# Header_and_OnboardConponents.net
KiCad netlist of a schematic drawn in Altium Designer
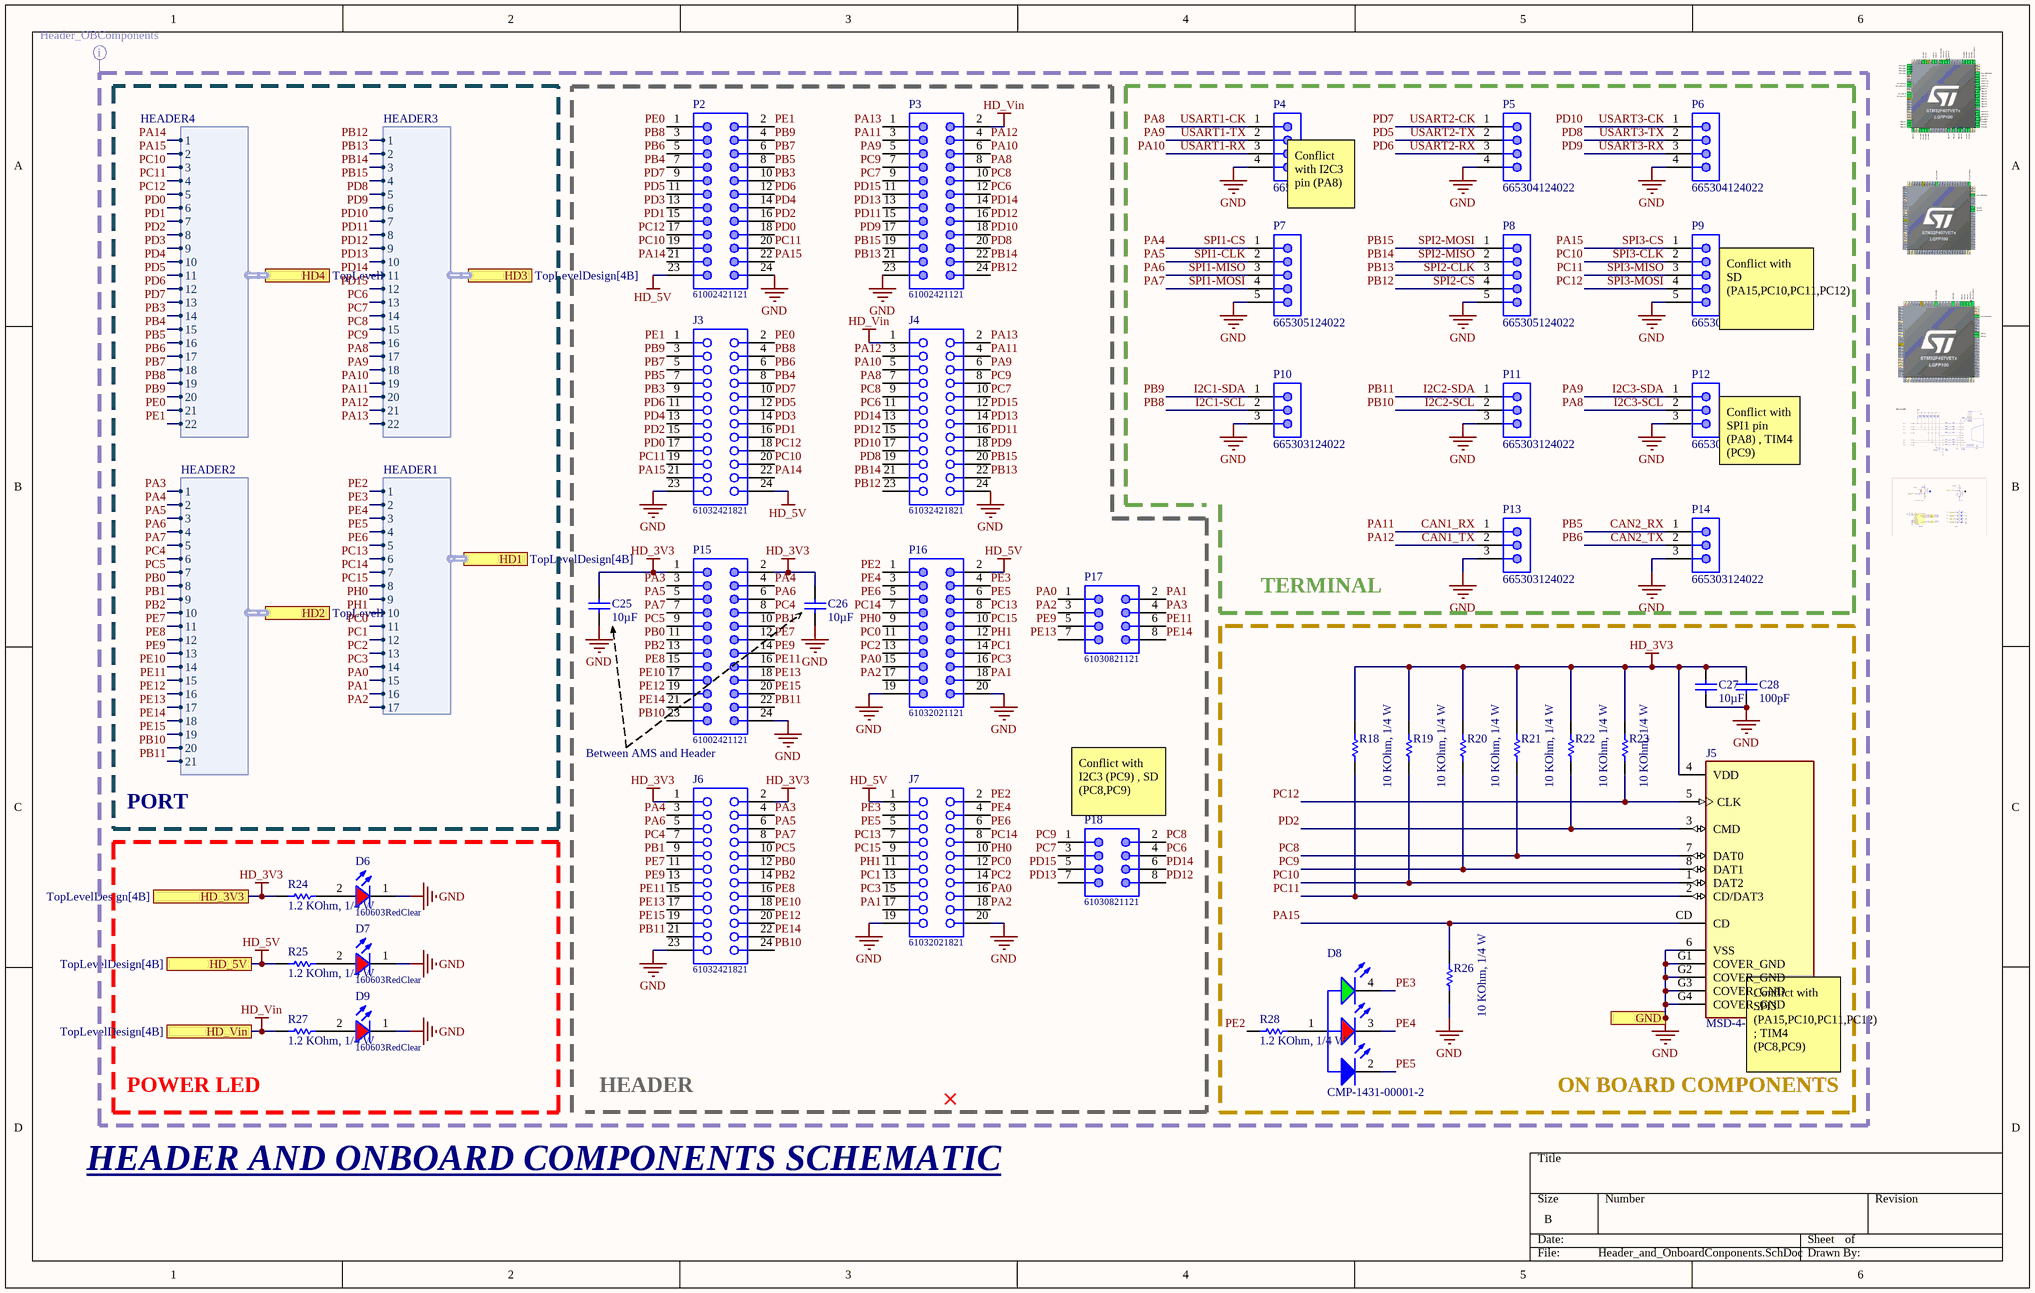
[diagram p0: Header_and_OnboardConponents.SchDoc]

(export (version "E")
  (design (tool "Eeschema 10.0.6"))
  (components
    (comp (ref "C25")
      (value "10µF")
      (footprint "CAP_0603")
      (description "CAP, size 0603, 10 uF, 10 VDC")
      (fields
        (field (name "TOLERANCE") "10%")
        (field (name "Comment") "0106031061010")
        (field (name "SOURCE") "Capacitor_0603_10_percent.SchLib")
      )
      (libsource (lib "Tin Tran") (part "010603475106.3"))
    )
    (comp (ref "C26")
      (value "10µF")
      (footprint "CAP_0603")
      (description "CAP, size 0603, 10 uF, 10 VDC")
      (fields
        (field (name "TOLERANCE") "10%")
        (field (name "Comment") "0106031061010")
        (field (name "SOURCE") "Capacitor_0603_10_percent.SchLib")
      )
      (libsource (lib "Tin Tran") (part "010603475106.3"))
    )
    (comp (ref "C27")
      (value "10µF")
      (footprint "CAP_0603")
      (description "CAP, size 0603, 10 uF, 10 VDC")
      (fields
        (field (name "TOLERANCE") "10%")
        (field (name "Comment") "0106031061010")
        (field (name "SOURCE") "Capacitor_0603_10_percent.SchLib")
      )
      (libsource (lib "Tin Tran") (part "010603475106.3"))
    )
    (comp (ref "C28")
      (value "100pF")
      (footprint "CAP_0603")
      (description "CAP, size 0603, 100 pF, 50 VDC")
      (fields
        (field (name "TOLERANCE") "5%")
        (field (name "Comment") "0106031010550")
        (field (name "SOURCE") "Capacitor_0603_5_percent.SchLib")
      )
      (libsource (lib "Tin Tran") (part "0106036820550"))
    )
    (comp (ref "D6")
      (value "160603RedClear")
      (footprint "WL-SMCW_0603_H=0.7mm")
      (description "WL-SMCW SMT Mono-color Chip LED Waterclear, size 0603, Red, 2V, 140deg")
      (libsource (lib "Tin Tran") (part "160603RedClear"))
    )
    (comp (ref "D7")
      (value "160603RedClear")
      (footprint "WL-SMCW_0603_H=0.7mm")
      (description "WL-SMCW SMT Mono-color Chip LED Waterclear, size 0603, Red, 2V, 140deg")
      (libsource (lib "Tin Tran") (part "160603RedClear"))
    )
    (comp (ref "D8")
      (value "CMP-1431-00001-2")
      (footprint "WL-SFTW_3528_150141M173100")
      (libsource (lib "Tin Tran") (part "CMP-1431-00001-2"))
    )
    (comp (ref "D9")
      (value "160603RedClear")
      (footprint "WL-SMCW_0603_H=0.7mm")
      (description "WL-SMCW SMT Mono-color Chip LED Waterclear, size 0603, Red, 2V, 140deg")
      (libsource (lib "Tin Tran") (part "160603RedClear"))
    )
    (comp (ref "J3")
      (value "61032421821")
      (footprint "61032421821")
      (description "WR-PHD Socket Header, SMT, pitch 2.54mm, Dual Row, Vertical, 24p")
      (fields (field (name "MANUFACTURER") "Wurth Elektronik"))
      (libsource (lib "Tin Tran") (part "613024243121"))
    )
    (comp (ref "J4")
      (value "61032421821")
      (footprint "61032421821")
      (description "WR-PHD Socket Header, SMT, pitch 2.54mm, Dual Row, Vertical, 24p")
      (fields (field (name "MANUFACTURER") "Wurth Elektronik"))
      (libsource (lib "Tin Tran") (part "613024243121"))
    )
    (comp (ref "J5")
      (value "MSD-4-A")
      (footprint "CUI_MSD-4-A")
      (fields (field (name "MF") "CUI Devices"))
      (libsource (lib "Tin Tran") (part "MSD-4-A"))
    )
    (comp (ref "J6")
      (value "61032421821")
      (footprint "61032421821")
      (description "WR-PHD Socket Header, SMT, pitch 2.54mm, Dual Row, Vertical, 24p")
      (fields (field (name "MANUFACTURER") "Wurth Elektronik"))
      (libsource (lib "Tin Tran") (part "613024243121"))
    )
    (comp (ref "J7")
      (value "61032021821")
      (footprint "61032021821")
      (description "WR-PHD Socket Header, SMT, pitch 2.54mm, Dual Row, Vertical, 20p")
      (fields (field (name "MANUFACTURER") "Wurth Elektronik"))
      (libsource (lib "Tin Tran") (part "613020243121"))
    )
    (comp (ref "P2")
      (value "61002421121")
      (footprint "61002421121")
      (description "WR-PHD Pin Header, SMT, pitch 2.54mm, Dual Row, Vertical, 24p")
      (fields (field (name "MANUFACTURER") "Wurth Elektronik"))
      (libsource (lib "Tin Tran") (part "61302421121"))
    )
    (comp (ref "P3")
      (value "61002421121")
      (footprint "61002421121")
      (description "WR-PHD Pin Header, SMT, pitch 2.54mm, Dual Row, Vertical, 24p")
      (fields (field (name "MANUFACTURER") "Wurth Elektronik"))
      (libsource (lib "Tin Tran") (part "61302421121"))
    )
    (comp (ref "P4")
      (value "665304124022")
      (footprint "665304124022")
      (description "WR-WTB SMT Male Vertical Shrouded Header, pitch 1mm, 4p")
      (fields (field (name "PUBLISHER") "Wurth Elektronik"))
      (libsource (lib "Tin Tran") (part "665304124022"))
    )
    (comp (ref "P5")
      (value "665304124022")
      (footprint "665304124022")
      (description "WR-WTB SMT Male Vertical Shrouded Header, pitch 1mm, 4p")
      (fields (field (name "PUBLISHER") "Wurth Elektronik"))
      (libsource (lib "Tin Tran") (part "665304124022"))
    )
    (comp (ref "P6")
      (value "665304124022")
      (footprint "665304124022")
      (description "WR-WTB SMT Male Vertical Shrouded Header, pitch 1mm, 4p")
      (fields (field (name "PUBLISHER") "Wurth Elektronik"))
      (libsource (lib "Tin Tran") (part "665304124022"))
    )
    (comp (ref "P7")
      (value "665305124022")
      (footprint "665305124022")
      (description "WR-WTB SMT Male Vertical Shrouded Header, pitch 1mm, 5p")
      (fields (field (name "PUBLISHER") "Wurth Elektronik"))
      (libsource (lib "Tin Tran") (part "665305124022"))
    )
    (comp (ref "P8")
      (value "665305124022")
      (footprint "665305124022")
      (description "WR-WTB SMT Male Vertical Shrouded Header, pitch 1mm, 5p")
      (fields (field (name "PUBLISHER") "Wurth Elektronik"))
      (libsource (lib "Tin Tran") (part "665305124022"))
    )
    (comp (ref "P9")
      (value "665305124022")
      (footprint "665305124022")
      (description "WR-WTB SMT Male Vertical Shrouded Header, pitch 1mm, 5p")
      (fields (field (name "PUBLISHER") "Wurth Elektronik"))
      (libsource (lib "Tin Tran") (part "665305124022"))
    )
    (comp (ref "P10")
      (value "665303124022")
      (footprint "665303124022")
      (description "WR-WTB SMT Male Vertical Shrouded Header, pitch 1mm, 3p")
      (fields (field (name "PUBLISHER") "Wurth Elektronik"))
      (libsource (lib "Tin Tran") (part "665303124022"))
    )
    (comp (ref "P11")
      (value "665303124022")
      (footprint "665303124022")
      (description "WR-WTB SMT Male Vertical Shrouded Header, pitch 1mm, 3p")
      (fields (field (name "PUBLISHER") "Wurth Elektronik"))
      (libsource (lib "Tin Tran") (part "665303124022"))
    )
    (comp (ref "P12")
      (value "665303124022")
      (footprint "665303124022")
      (description "WR-WTB SMT Male Vertical Shrouded Header, pitch 1mm, 3p")
      (fields (field (name "PUBLISHER") "Wurth Elektronik"))
      (libsource (lib "Tin Tran") (part "665303124022"))
    )
    (comp (ref "P13")
      (value "665303124022")
      (footprint "665303124022")
      (description "WR-WTB SMT Male Vertical Shrouded Header, pitch 1mm, 3p")
      (fields (field (name "PUBLISHER") "Wurth Elektronik"))
      (libsource (lib "Tin Tran") (part "665303124022"))
    )
    (comp (ref "P14")
      (value "665303124022")
      (footprint "665303124022")
      (description "WR-WTB SMT Male Vertical Shrouded Header, pitch 1mm, 3p")
      (fields (field (name "PUBLISHER") "Wurth Elektronik"))
      (libsource (lib "Tin Tran") (part "665303124022"))
    )
    (comp (ref "P15")
      (value "61002421121")
      (footprint "61002421121")
      (description "WR-PHD Pin Header, SMT, pitch 2.54mm, Dual Row, Vertical, 24p")
      (fields (field (name "MANUFACTURER") "Wurth Elektronik"))
      (libsource (lib "Tin Tran") (part "61302421121"))
    )
    (comp (ref "P16")
      (value "61032021121")
      (footprint "61032021121")
      (description "WR-PHD Pin Header, SMT, pitch 2.54mm, Dual Row, Vertical, 20p")
      (fields (field (name "MANUFACTURER") "Wurth Elektronik"))
      (libsource (lib "Tin Tran") (part "61302021121"))
    )
    (comp (ref "P17")
      (value "61030821121")
      (footprint "61030821121")
      (description "WR-PHD Pin Header, SMT, pitch 2.54mm, Dual Row, Vertical, 8p")
      (fields (field (name "MANUFACTURER") "Wurth Elektronik"))
      (libsource (lib "Tin Tran") (part "61300821121"))
    )
    (comp (ref "P18")
      (value "61030821121")
      (footprint "61030821121")
      (description "WR-PHD Pin Header, SMT, pitch 2.54mm, Dual Row, Vertical, 8p")
      (fields (field (name "MANUFACTURER") "Wurth Elektronik"))
      (libsource (lib "Tin Tran") (part "61300821121"))
    )
    (comp (ref "R18")
      (value "10 KOhm, 1/4 W")
      (footprint "resistor_0603")
      (description "RES, size 0603, 10 KOhm, 1/4 W")
      (fields (field (name "Comment") "0006031031"))
      (libsource (lib "Tin Tran") (part "00060371541"))
    )
    (comp (ref "R19")
      (value "10 KOhm, 1/4 W")
      (footprint "resistor_0603")
      (description "RES, size 0603, 10 KOhm, 1/4 W")
      (fields (field (name "Comment") "0006031031"))
      (libsource (lib "Tin Tran") (part "00060371541"))
    )
    (comp (ref "R20")
      (value "10 KOhm, 1/4 W")
      (footprint "resistor_0603")
      (description "RES, size 0603, 10 KOhm, 1/4 W")
      (fields (field (name "Comment") "0006031031"))
      (libsource (lib "Tin Tran") (part "00060371541"))
    )
    (comp (ref "R21")
      (value "10 KOhm, 1/4 W")
      (footprint "resistor_0603")
      (description "RES, size 0603, 10 KOhm, 1/4 W")
      (fields (field (name "Comment") "0006031031"))
      (libsource (lib "Tin Tran") (part "00060371541"))
    )
    (comp (ref "R22")
      (value "10 KOhm, 1/4 W")
      (footprint "resistor_0603")
      (description "RES, size 0603, 10 KOhm, 1/4 W")
      (fields (field (name "Comment") "0006031031"))
      (libsource (lib "Tin Tran") (part "00060371541"))
    )
    (comp (ref "R23")
      (value "10 KOhm, 1/4 W")
      (footprint "resistor_0603")
      (description "RES, size 0603, 10 KOhm, 1/4 W")
      (fields (field (name "Comment") "0006031031"))
      (libsource (lib "Tin Tran") (part "00060371541"))
    )
    (comp (ref "R24")
      (value "1.2 KOhm, 1/4 W")
      (footprint "resistor_0603")
      (description "RES, size 0603, 1.2 KOhm, 1/4 W")
      (fields (field (name "Comment") "0006031221"))
      (libsource (lib "Tin Tran") (part "00060371541"))
    )
    (comp (ref "R25")
      (value "1.2 KOhm, 1/4 W")
      (footprint "resistor_0603")
      (description "RES, size 0603, 1.2 KOhm, 1/4 W")
      (fields (field (name "Comment") "0006031221"))
      (libsource (lib "Tin Tran") (part "00060371541"))
    )
    (comp (ref "R26")
      (value "10 KOhm, 1/4 W")
      (footprint "resistor_0603")
      (description "RES, size 0603, 10 KOhm, 1/4 W")
      (fields (field (name "Comment") "0006031031"))
      (libsource (lib "Tin Tran") (part "00060371541"))
    )
    (comp (ref "R27")
      (value "1.2 KOhm, 1/4 W")
      (footprint "resistor_0603")
      (description "RES, size 0603, 1.2 KOhm, 1/4 W")
      (fields (field (name "Comment") "0006031221"))
      (libsource (lib "Tin Tran") (part "00060371541"))
    )
    (comp (ref "R28")
      (value "1.2 KOhm, 1/4 W")
      (footprint "resistor_0603")
      (description "RES, size 0603, 1.2 KOhm, 1/4 W")
      (fields (field (name "Comment") "0006031221"))
      (libsource (lib "Tin Tran") (part "00060371541"))
    )
  )
  (nets
    (net (code "5") (name "/CAN1_RX") (class "Default")
      (node (ref "J4") (pin "4") (pinfunction "4_4") (pintype "passive"))
      (node (ref "P13") (pin "1") (pinfunction "1_1") (pintype "passive"))
      (node (ref "P3") (pin "3") (pinfunction "3_3") (pintype "passive"))
    )
    (net (code "6") (name "/CAN1_TX") (class "Default")
      (node (ref "J4") (pin "3") (pinfunction "3_3") (pintype "passive"))
      (node (ref "P13") (pin "2") (pinfunction "2_2") (pintype "passive"))
      (node (ref "P3") (pin "4") (pinfunction "4_4") (pintype "passive"))
    )
    (net (code "7") (name "/CAN2_RX") (class "Default")
      (node (ref "J3") (pin "7") (pinfunction "7_7") (pintype "passive"))
      (node (ref "P14") (pin "1") (pinfunction "1_1") (pintype "passive"))
      (node (ref "P2") (pin "8") (pinfunction "8_8") (pintype "passive"))
    )
    (net (code "8") (name "/CAN2_TX") (class "Default")
      (node (ref "J3") (pin "6") (pinfunction "6_6") (pintype "passive"))
      (node (ref "P14") (pin "2") (pinfunction "2_2") (pintype "passive"))
      (node (ref "P2") (pin "5") (pinfunction "5_5") (pintype "passive"))
    )
    (net (code "9") (name "/I2C1-SCL") (class "Default")
      (node (ref "J3") (pin "4") (pinfunction "4_4") (pintype "passive"))
      (node (ref "P10") (pin "2") (pinfunction "2_2") (pintype "passive"))
      (node (ref "P2") (pin "3") (pinfunction "3_3") (pintype "passive"))
    )
    (net (code "10") (name "/I2C1-SDA") (class "Default")
      (node (ref "J3") (pin "3") (pinfunction "3_3") (pintype "passive"))
      (node (ref "P10") (pin "1") (pinfunction "1_1") (pintype "passive"))
      (node (ref "P2") (pin "4") (pinfunction "4_4") (pintype "passive"))
    )
    (net (code "11") (name "/I2C2-SCL") (class "Default")
      (node (ref "J6") (pin "24") (pinfunction "24_24") (pintype "passive"))
      (node (ref "P11") (pin "2") (pinfunction "2_2") (pintype "passive"))
      (node (ref "P15") (pin "23") (pinfunction "23_23") (pintype "passive"))
    )
    (net (code "12") (name "/I2C2-SDA") (class "Default")
      (node (ref "J6") (pin "21") (pinfunction "21_21") (pintype "passive"))
      (node (ref "P11") (pin "1") (pinfunction "1_1") (pintype "passive"))
      (node (ref "P15") (pin "22") (pinfunction "22_22") (pintype "passive"))
    )
    (net (code "13") (name "/I2C3-SCL") (class "Default")
      (node (ref "J4") (pin "7") (pinfunction "7_7") (pintype "passive"))
      (node (ref "P12") (pin "2") (pinfunction "2_2") (pintype "passive"))
      (node (ref "P3") (pin "8") (pinfunction "8_8") (pintype "passive"))
      (node (ref "P4") (pin "1") (pinfunction "1_1") (pintype "passive"))
    )
    (net (code "14") (name "/I2C3-SDA") (class "Default")
      (node (ref "J4") (pin "6") (pinfunction "6_6") (pintype "passive"))
      (node (ref "P12") (pin "1") (pinfunction "1_1") (pintype "passive"))
      (node (ref "P3") (pin "5") (pinfunction "5_5") (pintype "passive"))
      (node (ref "P4") (pin "2") (pinfunction "2_2") (pintype "passive"))
    )
    (net (code "15") (name "/PA0") (class "Default")
      (node (ref "J7") (pin "16") (pinfunction "16_16") (pintype "passive"))
      (node (ref "P16") (pin "15") (pinfunction "15_15") (pintype "passive"))
      (node (ref "P17") (pin "1") (pinfunction "1_1") (pintype "passive"))
    )
    (net (code "16") (name "/PA1") (class "Default")
      (node (ref "J7") (pin "17") (pinfunction "17_17") (pintype "passive"))
      (node (ref "P16") (pin "18") (pinfunction "18_18") (pintype "passive"))
      (node (ref "P17") (pin "2") (pinfunction "2_2") (pintype "passive"))
    )
    (net (code "17") (name "/PA2") (class "Default")
      (node (ref "J7") (pin "18") (pinfunction "18_18") (pintype "passive"))
      (node (ref "P16") (pin "17") (pinfunction "17_17") (pintype "passive"))
      (node (ref "P17") (pin "3") (pinfunction "3_3") (pintype "passive"))
    )
    (net (code "18") (name "/PA3") (class "Default")
      (node (ref "J6") (pin "4") (pinfunction "4_4") (pintype "passive"))
      (node (ref "P15") (pin "3") (pinfunction "3_3") (pintype "passive"))
      (node (ref "P17") (pin "4") (pinfunction "4_4") (pintype "passive"))
    )
    (net (code "19") (name "/PA4") (class "Default")
      (node (ref "J6") (pin "3") (pinfunction "3_3") (pintype "passive"))
      (node (ref "P15") (pin "4") (pinfunction "4_4") (pintype "passive"))
      (node (ref "P7") (pin "1") (pinfunction "1_1") (pintype "passive"))
    )
    (net (code "20") (name "/PA5") (class "Default")
      (node (ref "J6") (pin "6") (pinfunction "6_6") (pintype "passive"))
      (node (ref "P15") (pin "5") (pinfunction "5_5") (pintype "passive"))
      (node (ref "P7") (pin "2") (pinfunction "2_2") (pintype "passive"))
    )
    (net (code "21") (name "/PA6") (class "Default")
      (node (ref "J6") (pin "5") (pinfunction "5_5") (pintype "passive"))
      (node (ref "P15") (pin "6") (pinfunction "6_6") (pintype "passive"))
      (node (ref "P7") (pin "3") (pinfunction "3_3") (pintype "passive"))
    )
    (net (code "22") (name "/PA7") (class "Default")
      (node (ref "J6") (pin "8") (pinfunction "8_8") (pintype "passive"))
      (node (ref "P15") (pin "7") (pinfunction "7_7") (pintype "passive"))
      (node (ref "P7") (pin "4") (pinfunction "4_4") (pintype "passive"))
    )
    (net (code "23") (name "/PA10") (class "Default")
      (node (ref "J4") (pin "5") (pinfunction "5_5") (pintype "passive"))
      (node (ref "P3") (pin "6") (pinfunction "6_6") (pintype "passive"))
      (node (ref "P4") (pin "3") (pinfunction "3_3") (pintype "passive"))
    )
    (net (code "24") (name "/PA13") (class "Default")
      (node (ref "J4") (pin "2") (pinfunction "2_2") (pintype "passive"))
      (node (ref "P3") (pin "1") (pinfunction "1_1") (pintype "passive"))
    )
    (net (code "25") (name "/PA14") (class "Default")
      (node (ref "J3") (pin "22") (pinfunction "22_22") (pintype "passive"))
      (node (ref "P2") (pin "21") (pinfunction "21_21") (pintype "passive"))
    )
    (net (code "26") (name "/PA15") (class "Default")
      (node (ref "J3") (pin "21") (pinfunction "21_21") (pintype "passive"))
      (node (ref "J5") (pin "CD") (pinfunction "CD_CD") (pintype "passive"))
      (node (ref "P2") (pin "22") (pinfunction "22_22") (pintype "passive"))
      (node (ref "P9") (pin "1") (pinfunction "1_1") (pintype "passive"))
      (node (ref "R26") (pin "2") (pinfunction "2_2") (pintype "passive"))
    )
    (net (code "27") (name "/PB0") (class "Default")
      (node (ref "J6") (pin "12") (pinfunction "12_12") (pintype "passive"))
      (node (ref "P15") (pin "11") (pinfunction "11_11") (pintype "passive"))
    )
    (net (code "28") (name "/PB1") (class "Default")
      (node (ref "J6") (pin "9") (pinfunction "9_9") (pintype "passive"))
      (node (ref "P15") (pin "10") (pinfunction "10_10") (pintype "passive"))
    )
    (net (code "29") (name "/PB2") (class "Default")
      (node (ref "J6") (pin "14") (pinfunction "14_14") (pintype "passive"))
      (node (ref "P15") (pin "13") (pinfunction "13_13") (pintype "passive"))
    )
    (net (code "30") (name "/PB3") (class "Default")
      (node (ref "J3") (pin "9") (pinfunction "9_9") (pintype "passive"))
      (node (ref "P2") (pin "10") (pinfunction "10_10") (pintype "passive"))
    )
    (net (code "31") (name "/PB4") (class "Default")
      (node (ref "J3") (pin "8") (pinfunction "8_8") (pintype "passive"))
      (node (ref "P2") (pin "7") (pinfunction "7_7") (pintype "passive"))
    )
    (net (code "32") (name "/PB7") (class "Default")
      (node (ref "J3") (pin "5") (pinfunction "5_5") (pintype "passive"))
      (node (ref "P2") (pin "6") (pinfunction "6_6") (pintype "passive"))
    )
    (net (code "33") (name "/PB12") (class "Default")
      (node (ref "J4") (pin "23") (pinfunction "23_23") (pintype "passive"))
      (node (ref "P3") (pin "24") (pinfunction "24_24") (pintype "passive"))
      (node (ref "P8") (pin "4") (pinfunction "4_4") (pintype "passive"))
    )
    (net (code "34") (name "/PB13") (class "Default")
      (node (ref "J4") (pin "22") (pinfunction "22_22") (pintype "passive"))
      (node (ref "P3") (pin "21") (pinfunction "21_21") (pintype "passive"))
      (node (ref "P8") (pin "3") (pinfunction "3_3") (pintype "passive"))
    )
    (net (code "35") (name "/PB14") (class "Default")
      (node (ref "J4") (pin "21") (pinfunction "21_21") (pintype "passive"))
      (node (ref "P3") (pin "22") (pinfunction "22_22") (pintype "passive"))
      (node (ref "P8") (pin "2") (pinfunction "2_2") (pintype "passive"))
    )
    (net (code "36") (name "/PB15") (class "Default")
      (node (ref "J4") (pin "20") (pinfunction "20_20") (pintype "passive"))
      (node (ref "P3") (pin "19") (pinfunction "19_19") (pintype "passive"))
      (node (ref "P8") (pin "1") (pinfunction "1_1") (pintype "passive"))
    )
    (net (code "37") (name "/PC0") (class "Default")
      (node (ref "J7") (pin "12") (pinfunction "12_12") (pintype "passive"))
      (node (ref "P16") (pin "11") (pinfunction "11_11") (pintype "passive"))
    )
    (net (code "38") (name "/PC1") (class "Default")
      (node (ref "J7") (pin "13") (pinfunction "13_13") (pintype "passive"))
      (node (ref "P16") (pin "14") (pinfunction "14_14") (pintype "passive"))
    )
    (net (code "39") (name "/PC2") (class "Default")
      (node (ref "J7") (pin "14") (pinfunction "14_14") (pintype "passive"))
      (node (ref "P16") (pin "13") (pinfunction "13_13") (pintype "passive"))
    )
    (net (code "40") (name "/PC3") (class "Default")
      (node (ref "J7") (pin "15") (pinfunction "15_15") (pintype "passive"))
      (node (ref "P16") (pin "16") (pinfunction "16_16") (pintype "passive"))
    )
    (net (code "41") (name "/PC4") (class "Default")
      (node (ref "J6") (pin "7") (pinfunction "7_7") (pintype "passive"))
      (node (ref "P15") (pin "8") (pinfunction "8_8") (pintype "passive"))
    )
    (net (code "42") (name "/PC5") (class "Default")
      (node (ref "J6") (pin "10") (pinfunction "10_10") (pintype "passive"))
      (node (ref "P15") (pin "9") (pinfunction "9_9") (pintype "passive"))
    )
    (net (code "43") (name "/PC6") (class "Default")
      (node (ref "J4") (pin "11") (pinfunction "11_11") (pintype "passive"))
      (node (ref "P18") (pin "4") (pinfunction "4_4") (pintype "passive"))
      (node (ref "P3") (pin "12") (pinfunction "12_12") (pintype "passive"))
    )
    (net (code "44") (name "/PC7") (class "Default")
      (node (ref "J4") (pin "10") (pinfunction "10_10") (pintype "passive"))
      (node (ref "P18") (pin "3") (pinfunction "3_3") (pintype "passive"))
      (node (ref "P3") (pin "9") (pinfunction "9_9") (pintype "passive"))
    )
    (net (code "45") (name "/PC8") (class "Default")
      (node (ref "J4") (pin "9") (pinfunction "9_9") (pintype "passive"))
      (node (ref "J5") (pin "7") (pinfunction "DAT0_7") (pintype "bidirectional"))
      (node (ref "P18") (pin "2") (pinfunction "2_2") (pintype "passive"))
      (node (ref "P3") (pin "10") (pinfunction "10_10") (pintype "passive"))
      (node (ref "R21") (pin "1") (pinfunction "1_1") (pintype "passive"))
    )
    (net (code "46") (name "/PC9") (class "Default")
      (node (ref "J4") (pin "8") (pinfunction "8_8") (pintype "passive"))
      (node (ref "J5") (pin "8") (pinfunction "DAT1_8") (pintype "bidirectional"))
      (node (ref "P18") (pin "1") (pinfunction "1_1") (pintype "passive"))
      (node (ref "P3") (pin "7") (pinfunction "7_7") (pintype "passive"))
      (node (ref "R20") (pin "1") (pinfunction "1_1") (pintype "passive"))
    )
    (net (code "47") (name "/PC10") (class "Default")
      (node (ref "J3") (pin "20") (pinfunction "20_20") (pintype "passive"))
      (node (ref "J5") (pin "1") (pinfunction "DAT2_1") (pintype "bidirectional"))
      (node (ref "P2") (pin "19") (pinfunction "19_19") (pintype "passive"))
      (node (ref "P9") (pin "2") (pinfunction "2_2") (pintype "passive"))
      (node (ref "R19") (pin "1") (pinfunction "1_1") (pintype "passive"))
    )
    (net (code "48") (name "/PC11") (class "Default")
      (node (ref "J3") (pin "19") (pinfunction "19_19") (pintype "passive"))
      (node (ref "J5") (pin "2") (pinfunction "CD/DAT3_2") (pintype "bidirectional"))
      (node (ref "P2") (pin "20") (pinfunction "20_20") (pintype "passive"))
      (node (ref "P9") (pin "3") (pinfunction "3_3") (pintype "passive"))
      (node (ref "R18") (pin "1") (pinfunction "1_1") (pintype "passive"))
    )
    (net (code "49") (name "/PC12") (class "Default")
      (node (ref "J3") (pin "18") (pinfunction "18_18") (pintype "passive"))
      (node (ref "J5") (pin "5") (pinfunction "CLK_5") (pintype "input"))
      (node (ref "P2") (pin "17") (pinfunction "17_17") (pintype "passive"))
      (node (ref "P9") (pin "4") (pinfunction "4_4") (pintype "passive"))
      (node (ref "R23") (pin "1") (pinfunction "1_1") (pintype "passive"))
    )
    (net (code "50") (name "/PC13") (class "Default")
      (node (ref "J7") (pin "7") (pinfunction "7_7") (pintype "passive"))
      (node (ref "P16") (pin "8") (pinfunction "8_8") (pintype "passive"))
    )
    (net (code "51") (name "/PC14") (class "Default")
      (node (ref "J7") (pin "8") (pinfunction "8_8") (pintype "passive"))
      (node (ref "P16") (pin "7") (pinfunction "7_7") (pintype "passive"))
    )
    (net (code "52") (name "/PC15") (class "Default")
      (node (ref "J7") (pin "9") (pinfunction "9_9") (pintype "passive"))
      (node (ref "P16") (pin "10") (pinfunction "10_10") (pintype "passive"))
    )
    (net (code "53") (name "/PD0") (class "Default")
      (node (ref "J3") (pin "17") (pinfunction "17_17") (pintype "passive"))
      (node (ref "P2") (pin "18") (pinfunction "18_18") (pintype "passive"))
    )
    (net (code "54") (name "/PD1") (class "Default")
      (node (ref "J3") (pin "16") (pinfunction "16_16") (pintype "passive"))
      (node (ref "P2") (pin "15") (pinfunction "15_15") (pintype "passive"))
    )
    (net (code "55") (name "/PD2") (class "Default")
      (node (ref "J3") (pin "15") (pinfunction "15_15") (pintype "passive"))
      (node (ref "J5") (pin "3") (pinfunction "CMD_3") (pintype "bidirectional"))
      (node (ref "P2") (pin "16") (pinfunction "16_16") (pintype "passive"))
      (node (ref "R22") (pin "1") (pinfunction "1_1") (pintype "passive"))
    )
    (net (code "56") (name "/PD3") (class "Default")
      (node (ref "J3") (pin "14") (pinfunction "14_14") (pintype "passive"))
      (node (ref "P2") (pin "13") (pinfunction "13_13") (pintype "passive"))
    )
    (net (code "57") (name "/PD4") (class "Default")
      (node (ref "J3") (pin "13") (pinfunction "13_13") (pintype "passive"))
      (node (ref "P2") (pin "14") (pinfunction "14_14") (pintype "passive"))
    )
    (net (code "58") (name "/PD5") (class "Default")
      (node (ref "J3") (pin "12") (pinfunction "12_12") (pintype "passive"))
      (node (ref "P2") (pin "11") (pinfunction "11_11") (pintype "passive"))
      (node (ref "P5") (pin "2") (pinfunction "2_2") (pintype "passive"))
    )
    (net (code "59") (name "/PD6") (class "Default")
      (node (ref "J3") (pin "11") (pinfunction "11_11") (pintype "passive"))
      (node (ref "P2") (pin "12") (pinfunction "12_12") (pintype "passive"))
      (node (ref "P5") (pin "3") (pinfunction "3_3") (pintype "passive"))
    )
    (net (code "60") (name "/PD7") (class "Default")
      (node (ref "J3") (pin "10") (pinfunction "10_10") (pintype "passive"))
      (node (ref "P2") (pin "9") (pinfunction "9_9") (pintype "passive"))
      (node (ref "P5") (pin "1") (pinfunction "1_1") (pintype "passive"))
    )
    (net (code "61") (name "/PD8") (class "Default")
      (node (ref "J4") (pin "19") (pinfunction "19_19") (pintype "passive"))
      (node (ref "P3") (pin "20") (pinfunction "20_20") (pintype "passive"))
      (node (ref "P6") (pin "2") (pinfunction "2_2") (pintype "passive"))
    )
    (net (code "62") (name "/PD9") (class "Default")
      (node (ref "J4") (pin "18") (pinfunction "18_18") (pintype "passive"))
      (node (ref "P3") (pin "17") (pinfunction "17_17") (pintype "passive"))
      (node (ref "P6") (pin "3") (pinfunction "3_3") (pintype "passive"))
    )
    (net (code "63") (name "/PD10") (class "Default")
      (node (ref "J4") (pin "17") (pinfunction "17_17") (pintype "passive"))
      (node (ref "P3") (pin "18") (pinfunction "18_18") (pintype "passive"))
      (node (ref "P6") (pin "1") (pinfunction "1_1") (pintype "passive"))
    )
    (net (code "64") (name "/PD11") (class "Default")
      (node (ref "J4") (pin "16") (pinfunction "16_16") (pintype "passive"))
      (node (ref "P3") (pin "15") (pinfunction "15_15") (pintype "passive"))
    )
    (net (code "65") (name "/PD12") (class "Default")
      (node (ref "J4") (pin "15") (pinfunction "15_15") (pintype "passive"))
      (node (ref "P18") (pin "8") (pinfunction "8_8") (pintype "passive"))
      (node (ref "P3") (pin "16") (pinfunction "16_16") (pintype "passive"))
    )
    (net (code "66") (name "/PD13") (class "Default")
      (node (ref "J4") (pin "14") (pinfunction "14_14") (pintype "passive"))
      (node (ref "P18") (pin "7") (pinfunction "7_7") (pintype "passive"))
      (node (ref "P3") (pin "13") (pinfunction "13_13") (pintype "passive"))
    )
    (net (code "67") (name "/PD14") (class "Default")
      (node (ref "J4") (pin "13") (pinfunction "13_13") (pintype "passive"))
      (node (ref "P18") (pin "6") (pinfunction "6_6") (pintype "passive"))
      (node (ref "P3") (pin "14") (pinfunction "14_14") (pintype "passive"))
    )
    (net (code "68") (name "/PD15") (class "Default")
      (node (ref "J4") (pin "12") (pinfunction "12_12") (pintype "passive"))
      (node (ref "P18") (pin "5") (pinfunction "5_5") (pintype "passive"))
      (node (ref "P3") (pin "11") (pinfunction "11_11") (pintype "passive"))
    )
    (net (code "69") (name "/PE0") (class "Default")
      (node (ref "J3") (pin "2") (pinfunction "2_2") (pintype "passive"))
      (node (ref "P2") (pin "1") (pinfunction "1_1") (pintype "passive"))
    )
    (net (code "70") (name "/PE1") (class "Default")
      (node (ref "J3") (pin "1") (pinfunction "1_1") (pintype "passive"))
      (node (ref "P2") (pin "2") (pinfunction "2_2") (pintype "passive"))
    )
    (net (code "71") (name "/PE2") (class "Default")
      (node (ref "J7") (pin "2") (pinfunction "2_2") (pintype "passive"))
      (node (ref "P16") (pin "1") (pinfunction "1_1") (pintype "passive"))
      (node (ref "R28") (pin "1") (pinfunction "1_1") (pintype "passive"))
    )
    (net (code "72") (name "/PE3") (class "Default")
      (node (ref "D8") (pin "4") (pinfunction "K_4") (pintype "passive"))
      (node (ref "J7") (pin "3") (pinfunction "3_3") (pintype "passive"))
      (node (ref "P16") (pin "4") (pinfunction "4_4") (pintype "passive"))
    )
    (net (code "73") (name "/PE4") (class "Default")
      (node (ref "D8") (pin "3") (pinfunction "K_3") (pintype "passive"))
      (node (ref "J7") (pin "4") (pinfunction "4_4") (pintype "passive"))
      (node (ref "P16") (pin "3") (pinfunction "3_3") (pintype "passive"))
    )
    (net (code "74") (name "/PE5") (class "Default")
      (node (ref "D8") (pin "2") (pinfunction "K_2") (pintype "passive"))
      (node (ref "J7") (pin "5") (pinfunction "5_5") (pintype "passive"))
      (node (ref "P16") (pin "6") (pinfunction "6_6") (pintype "passive"))
    )
    (net (code "75") (name "/PE6") (class "Default")
      (node (ref "J7") (pin "6") (pinfunction "6_6") (pintype "passive"))
      (node (ref "P16") (pin "5") (pinfunction "5_5") (pintype "passive"))
    )
    (net (code "76") (name "/PE7") (class "Default")
      (node (ref "J6") (pin "11") (pinfunction "11_11") (pintype "passive"))
      (node (ref "P15") (pin "12") (pinfunction "12_12") (pintype "passive"))
    )
    (net (code "77") (name "/PE8") (class "Default")
      (node (ref "J6") (pin "16") (pinfunction "16_16") (pintype "passive"))
      (node (ref "P15") (pin "15") (pinfunction "15_15") (pintype "passive"))
    )
    (net (code "78") (name "/PE9") (class "Default")
      (node (ref "J6") (pin "13") (pinfunction "13_13") (pintype "passive"))
      (node (ref "P15") (pin "14") (pinfunction "14_14") (pintype "passive"))
      (node (ref "P17") (pin "5") (pinfunction "5_5") (pintype "passive"))
    )
    (net (code "79") (name "/PE10") (class "Default")
      (node (ref "J6") (pin "18") (pinfunction "18_18") (pintype "passive"))
      (node (ref "P15") (pin "17") (pinfunction "17_17") (pintype "passive"))
    )
    (net (code "80") (name "/PE11") (class "Default")
      (node (ref "J6") (pin "15") (pinfunction "15_15") (pintype "passive"))
      (node (ref "P15") (pin "16") (pinfunction "16_16") (pintype "passive"))
      (node (ref "P17") (pin "6") (pinfunction "6_6") (pintype "passive"))
    )
    (net (code "81") (name "/PE12") (class "Default")
      (node (ref "J6") (pin "20") (pinfunction "20_20") (pintype "passive"))
      (node (ref "P15") (pin "19") (pinfunction "19_19") (pintype "passive"))
    )
    (net (code "82") (name "/PE13") (class "Default")
      (node (ref "J6") (pin "17") (pinfunction "17_17") (pintype "passive"))
      (node (ref "P15") (pin "18") (pinfunction "18_18") (pintype "passive"))
      (node (ref "P17") (pin "7") (pinfunction "7_7") (pintype "passive"))
    )
    (net (code "83") (name "/PE14") (class "Default")
      (node (ref "J6") (pin "22") (pinfunction "22_22") (pintype "passive"))
      (node (ref "P15") (pin "21") (pinfunction "21_21") (pintype "passive"))
      (node (ref "P17") (pin "8") (pinfunction "8_8") (pintype "passive"))
    )
    (net (code "84") (name "/PE15") (class "Default")
      (node (ref "J6") (pin "19") (pinfunction "19_19") (pintype "passive"))
      (node (ref "P15") (pin "20") (pinfunction "20_20") (pintype "passive"))
    )
    (net (code "85") (name "/PH0") (class "Default")
      (node (ref "J7") (pin "10") (pinfunction "10_10") (pintype "passive"))
      (node (ref "P16") (pin "9") (pinfunction "9_9") (pintype "passive"))
    )
    (net (code "86") (name "/PH1") (class "Default")
      (node (ref "J7") (pin "11") (pinfunction "11_11") (pintype "passive"))
      (node (ref "P16") (pin "12") (pinfunction "12_12") (pintype "passive"))
    )
    (net (code "91") (name "GND") (class "Default")
      (node (ref "C25") (pin "1") (pinfunction "1_1") (pintype "passive"))
      (node (ref "C26") (pin "1") (pinfunction "1_1") (pintype "passive"))
      (node (ref "C27") (pin "1") (pinfunction "1_1") (pintype "passive"))
      (node (ref "C28") (pin "1") (pinfunction "1_1") (pintype "passive"))
      (node (ref "D6") (pin "1") (pinfunction "K_1") (pintype "passive"))
      (node (ref "D7") (pin "1") (pinfunction "K_1") (pintype "passive"))
      (node (ref "D9") (pin "1") (pinfunction "K_1") (pintype "passive"))
      (node (ref "J3") (pin "23") (pinfunction "23_23") (pintype "passive"))
      (node (ref "J4") (pin "24") (pinfunction "24_24") (pintype "passive"))
      (node (ref "J5") (pin "6") (pinfunction "VSS_6") (pintype "power_in"))
      (node (ref "J5") (pin "G1") (pinfunction "COVER_GND_G1") (pintype "power_in"))
      (node (ref "J5") (pin "G2") (pinfunction "COVER_GND_G2") (pintype "power_in"))
      (node (ref "J5") (pin "G3") (pinfunction "COVER_GND_G3") (pintype "power_in"))
      (node (ref "J5") (pin "G4") (pinfunction "COVER_GND_G4") (pintype "power_in"))
      (node (ref "J6") (pin "23") (pinfunction "23_23") (pintype "passive"))
      (node (ref "J7") (pin "19") (pinfunction "19_19") (pintype "passive"))
      (node (ref "J7") (pin "20") (pinfunction "20_20") (pintype "passive"))
      (node (ref "P10") (pin "3") (pinfunction "3_3") (pintype "passive"))
      (node (ref "P11") (pin "3") (pinfunction "3_3") (pintype "passive"))
      (node (ref "P12") (pin "3") (pinfunction "3_3") (pintype "passive"))
      (node (ref "P13") (pin "3") (pinfunction "3_3") (pintype "passive"))
      (node (ref "P14") (pin "3") (pinfunction "3_3") (pintype "passive"))
      (node (ref "P15") (pin "24") (pinfunction "24_24") (pintype "passive"))
      (node (ref "P16") (pin "19") (pinfunction "19_19") (pintype "passive"))
      (node (ref "P16") (pin "20") (pinfunction "20_20") (pintype "passive"))
      (node (ref "P2") (pin "24") (pinfunction "24_24") (pintype "passive"))
      (node (ref "P3") (pin "23") (pinfunction "23_23") (pintype "passive"))
      (node (ref "P4") (pin "4") (pinfunction "4_4") (pintype "passive"))
      (node (ref "P5") (pin "4") (pinfunction "4_4") (pintype "passive"))
      (node (ref "P6") (pin "4") (pinfunction "4_4") (pintype "passive"))
      (node (ref "P7") (pin "5") (pinfunction "5_5") (pintype "passive"))
      (node (ref "P8") (pin "5") (pinfunction "5_5") (pintype "passive"))
      (node (ref "P9") (pin "5") (pinfunction "5_5") (pintype "passive"))
      (node (ref "R26") (pin "1") (pinfunction "1_1") (pintype "passive"))
    )
    (net (code "92") (name "HD_3V3") (class "Default")
      (node (ref "C25") (pin "2") (pinfunction "2_2") (pintype "passive"))
      (node (ref "C26") (pin "2") (pinfunction "2_2") (pintype "passive"))
      (node (ref "C27") (pin "2") (pinfunction "2_2") (pintype "passive"))
      (node (ref "C28") (pin "2") (pinfunction "2_2") (pintype "passive"))
      (node (ref "J5") (pin "4") (pinfunction "VDD_4") (pintype "power_in"))
      (node (ref "J6") (pin "1") (pinfunction "1_1") (pintype "passive"))
      (node (ref "J6") (pin "2") (pinfunction "2_2") (pintype "passive"))
      (node (ref "P15") (pin "1") (pinfunction "1_1") (pintype "passive"))
      (node (ref "P15") (pin "2") (pinfunction "2_2") (pintype "passive"))
      (node (ref "R18") (pin "2") (pinfunction "2_2") (pintype "passive"))
      (node (ref "R19") (pin "2") (pinfunction "2_2") (pintype "passive"))
      (node (ref "R20") (pin "2") (pinfunction "2_2") (pintype "passive"))
      (node (ref "R21") (pin "2") (pinfunction "2_2") (pintype "passive"))
      (node (ref "R22") (pin "2") (pinfunction "2_2") (pintype "passive"))
      (node (ref "R23") (pin "2") (pinfunction "2_2") (pintype "passive"))
      (node (ref "R24") (pin "2") (pinfunction "2_2") (pintype "passive"))
    )
    (net (code "93") (name "HD_5V") (class "Default")
      (node (ref "J3") (pin "24") (pinfunction "24_24") (pintype "passive"))
      (node (ref "J7") (pin "1") (pinfunction "1_1") (pintype "passive"))
      (node (ref "P16") (pin "2") (pinfunction "2_2") (pintype "passive"))
      (node (ref "P2") (pin "23") (pinfunction "23_23") (pintype "passive"))
      (node (ref "R25") (pin "2") (pinfunction "2_2") (pintype "passive"))
    )
    (net (code "94") (name "HD_Vin") (class "Default")
      (node (ref "J4") (pin "1") (pinfunction "1_1") (pintype "passive"))
      (node (ref "P3") (pin "2") (pinfunction "2_2") (pintype "passive"))
      (node (ref "R27") (pin "2") (pinfunction "2_2") (pintype "passive"))
    )
    (net (code "95") (name "Net-(D6-A)") (class "Default")
      (node (ref "D6") (pin "2") (pinfunction "A_2") (pintype "passive"))
      (node (ref "R24") (pin "1") (pinfunction "1_1") (pintype "passive"))
    )
    (net (code "96") (name "Net-(D7-A)") (class "Default")
      (node (ref "D7") (pin "2") (pinfunction "A_2") (pintype "passive"))
      (node (ref "R25") (pin "1") (pinfunction "1_1") (pintype "passive"))
    )
    (net (code "97") (name "Net-(D8-A)") (class "Default")
      (node (ref "D8") (pin "1") (pinfunction "A_1") (pintype "passive"))
      (node (ref "R28") (pin "2") (pinfunction "2_2") (pintype "passive"))
    )
    (net (code "98") (name "Net-(D9-A)") (class "Default")
      (node (ref "D9") (pin "2") (pinfunction "A_2") (pintype "passive"))
      (node (ref "R27") (pin "1") (pinfunction "1_1") (pintype "passive"))
    )
  )
)
